# HC32F005.net
KiCad netlist of a schematic drawn in Altium Designer
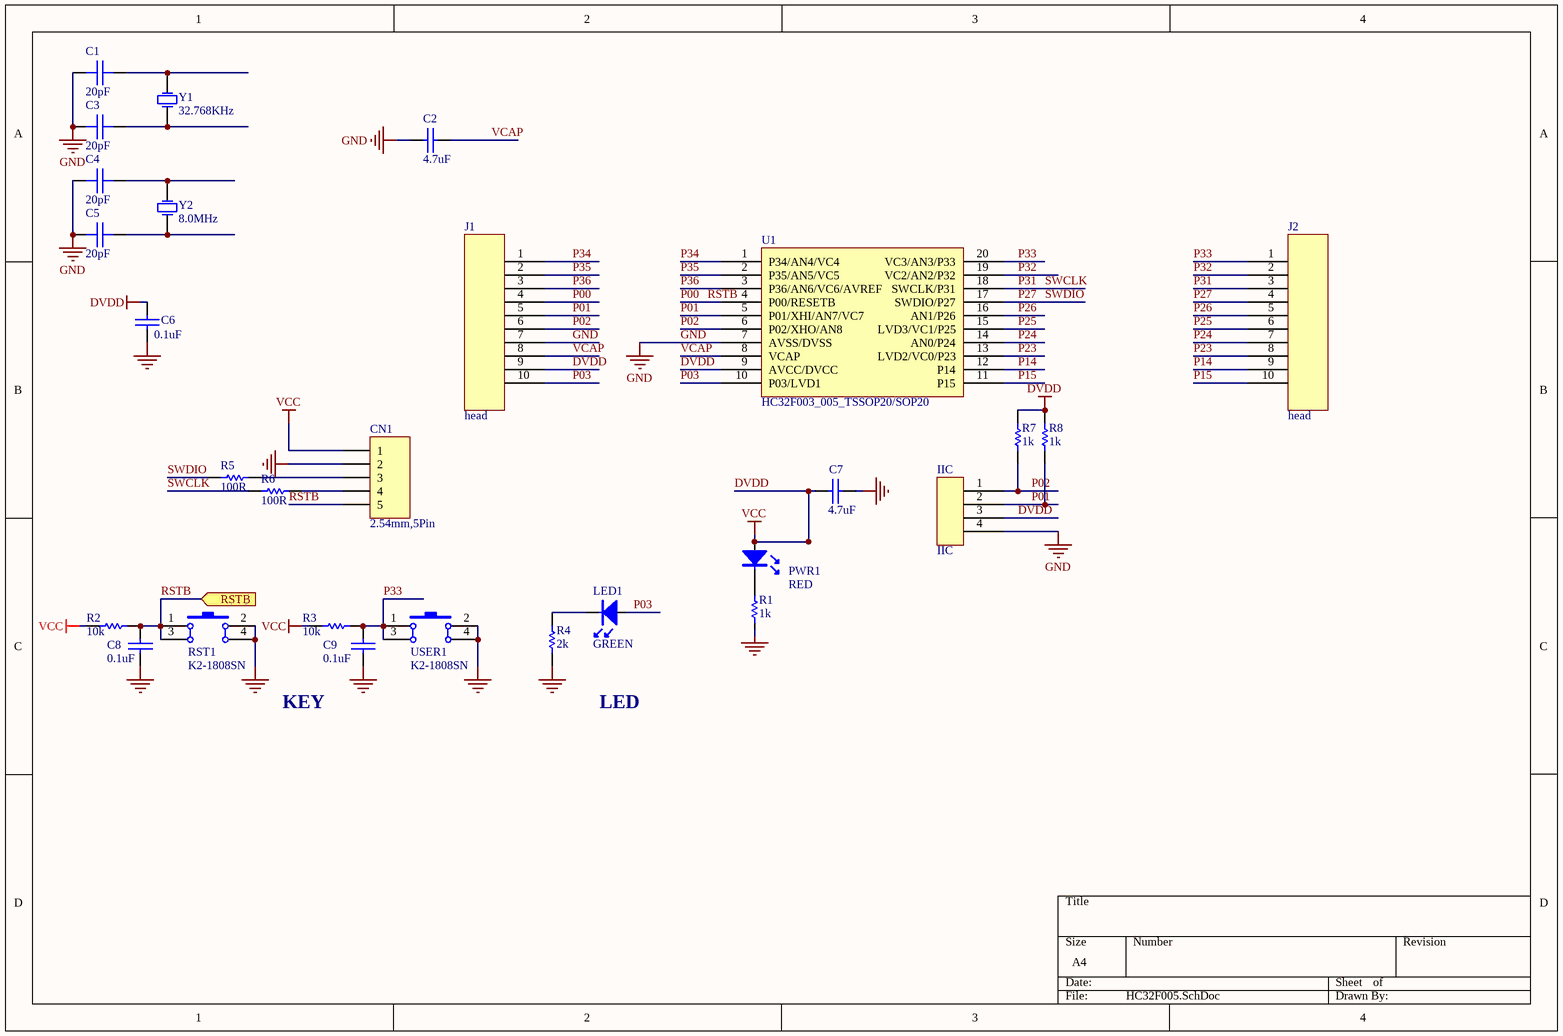
[diagram p0: HC32F005.SchDoc]

(export (version "E")
  (design (tool "Eeschema 10.0.6"))
  (components
    (comp (ref "C1")
      (value "20pF")
      (footprint "C0603")
      (description "Capacitor without polarity")
      (libsource (lib "STK-HC32L110_F003_005-TSSOP20-V2.0") (part "C_no pol"))
    )
    (comp (ref "C2")
      (value "4.7uF")
      (footprint "C0603")
      (description "Capacitor")
      (libsource (lib "STK-HC32L110_F003_005-TSSOP20-V2.0") (part "CAP-CC(SMD)"))
    )
    (comp (ref "C3")
      (value "20pF")
      (footprint "C0603")
      (description "Capacitor without polarity")
      (libsource (lib "STK-HC32L110_F003_005-TSSOP20-V2.0") (part "C_no pol"))
    )
    (comp (ref "C4")
      (value "20pF")
      (footprint "C0603")
      (description "Capacitor without polarity")
      (libsource (lib "STK-HC32L110_F003_005-TSSOP20-V2.0") (part "C_no pol"))
    )
    (comp (ref "C5")
      (value "20pF")
      (footprint "C0603")
      (description "Capacitor without polarity")
      (libsource (lib "STK-HC32L110_F003_005-TSSOP20-V2.0") (part "C_no pol"))
    )
    (comp (ref "C6")
      (value "0.1uF")
      (footprint "C0603")
      (description "Ceramic Capacitor,0603")
      (libsource (lib "MyLib_Altium") (part "CAP-CC(SMD)"))
    )
    (comp (ref "C7")
      (value "4.7uF")
      (footprint "C0603")
      (description "Ceramic Capacitor,0603")
      (libsource (lib "MyLib_Altium") (part "CAP-CC(SMD)"))
    )
    (comp (ref "C8")
      (value "0.1uF")
      (footprint "C0603")
      (description "Ceramic Capacitor,0603")
      (libsource (lib "MyLib_Altium") (part "CAP-CC(SMD)"))
    )
    (comp (ref "C9")
      (value "0.1uF")
      (footprint "C0603")
      (description "Ceramic Capacitor,0603")
      (libsource (lib "MyLib_Altium") (part "CAP-CC(SMD)"))
    )
    (comp (ref "CN1")
      (value "2.54mm,5Pin")
      (footprint "HDR1X5")
      (description "Header, 5-Pin")
      (fields (field (name "PUBLISHER") "Altium Limited"))
      (libsource (lib "STK-HC32L110_F003_005-TSSOP20-V2.0") (part "Header 5"))
    )
    (comp (ref "IIC")
      (value "IIC")
      (footprint "HDR1X4")
      (libsource (lib "altium-import") (part "root_0_IIC_"))
    )
    (comp (ref "J1")
      (value "head")
      (footprint "HDR1*10")
      (libsource (lib "altium-import") (part "root_0_mirrored_Component_1_"))
    )
    (comp (ref "J2")
      (value "head")
      (footprint "HC32F005:HDR1*10")
      (libsource (lib "altium-import") (part "root_0_Component_1_"))
    )
    (comp (ref "LED1") (value "GREEN") (footprint "LED0603") (libsource (lib "MyLib_Altium") (part "LED")))
    (comp (ref "PWR1") (value "RED") (footprint "LED0603") (libsource (lib "MyLib_Altium") (part "LED")))
    (comp (ref "R1")
      (value "1k")
      (footprint "R0603")
      (description "Resister,0603,5%")
      (libsource (lib "MyLib_Altium") (part "RES"))
    )
    (comp (ref "R2")
      (value "10k")
      (footprint "R0603")
      (description "Resister,0603,5%")
      (libsource (lib "MyLib_Altium") (part "RES"))
    )
    (comp (ref "R3")
      (value "10k")
      (footprint "R0603")
      (description "Resister,0603,5%")
      (libsource (lib "MyLib_Altium") (part "RES"))
    )
    (comp (ref "R4")
      (value "2k")
      (footprint "R0603")
      (description "Resister,0603,5%")
      (libsource (lib "MyLib_Altium") (part "RES"))
    )
    (comp (ref "R5")
      (value "100R")
      (footprint "R0603")
      (description "Resister,0603,5%")
      (libsource (lib "MyLib_Altium") (part "RES"))
    )
    (comp (ref "R6")
      (value "100R")
      (footprint "R0603")
      (description "Resister,0603,5%")
      (libsource (lib "MyLib_Altium") (part "RES"))
    )
    (comp (ref "R7")
      (value "1k")
      (footprint "R0603")
      (description "Resister,0603,5%")
      (libsource (lib "MyLib_Altium") (part "RES"))
    )
    (comp (ref "R8")
      (value "1k")
      (footprint "R0603")
      (description "Resister,0603,5%")
      (libsource (lib "MyLib_Altium") (part "RES"))
    )
    (comp (ref "RST1")
      (value "K2-1808SN")
      (footprint "STK-HC32L110_F003_005-TSSOP20-V2.01:PUSHBUTTON-4.2*3.25")
      (description "SMD button")
      (libsource (lib "MyLib_Altium") (part "Button-SMD-6*6"))
    )
    (comp (ref "U1")
      (value "HC32F003_005_TSSOP20/SOP20")
      (footprint "STK-HC32L110_F003_005-TSSOP20-V2.01:TSSOP-20")
      (libsource (lib "HC32L110_F003_005") (part "HC32F003_005_TSSOP20/SOP20"))
    )
    (comp (ref "USER1")
      (value "K2-1808SN")
      (footprint "PUSHBUTTON-4.2*3.25")
      (description "SMD button")
      (libsource (lib "MyLib_Altium") (part "Button-SMD-6*6"))
    )
    (comp (ref "Y1")
      (value "32.768KHz")
      (footprint "32.768K")
      (description "4.0000MHz")
      (libsource (lib "STK-HC32L110_F003_005-TSSOP20-V2.0") (part "Crystal_1"))
    )
    (comp (ref "Y2")
      (value "8.0MHz")
      (footprint "49s")
      (description "4.0000MHz")
      (libsource (lib "STK-HC32L110_F003_005-TSSOP20-V2.0") (part "Crystal"))
    )
  )
  (nets
    (net (code "1") (name "/P00") (class "Default")
      (node (ref "C8") (pin "1") (pinfunction "1_1") (pintype "passive"))
      (node (ref "CN1") (pin "5") (pinfunction "5_5") (pintype "passive"))
      (node (ref "J1") (pin "4") (pinfunction "13_4") (pintype "passive"))
      (node (ref "R2") (pin "2") (pinfunction "2_2") (pintype "passive"))
      (node (ref "RST1") (pin "1") (pinfunction "1_1") (pintype "passive"))
      (node (ref "RST1") (pin "3") (pinfunction "3_3") (pintype "passive"))
      (node (ref "U1") (pin "4") (pinfunction "P00/RESETB_4") (pintype "passive"))
    )
    (net (code "2") (name "/P01") (class "Default")
      (node (ref "IIC") (pin "2") (pinfunction "2_2") (pintype "passive"))
      (node (ref "J1") (pin "5") (pinfunction "14_5") (pintype "passive"))
      (node (ref "R8") (pin "2") (pinfunction "2_2") (pintype "passive"))
      (node (ref "U1") (pin "5") (pinfunction "P01/XHI/AN7/VC7_5") (pintype "passive"))
    )
    (net (code "3") (name "/P02") (class "Default")
      (node (ref "IIC") (pin "1") (pinfunction "1_1") (pintype "passive"))
      (node (ref "J1") (pin "6") (pinfunction "15_6") (pintype "passive"))
      (node (ref "R7") (pin "2") (pinfunction "2_2") (pintype "passive"))
      (node (ref "U1") (pin "6") (pinfunction "P02/XHO/AN8_6") (pintype "passive"))
    )
    (net (code "4") (name "/P03") (class "Default")
      (node (ref "J1") (pin "10") (pinfunction "19_10") (pintype "passive"))
      (node (ref "LED1") (pin "1") (pinfunction "A_1") (pintype "passive"))
      (node (ref "U1") (pin "10") (pinfunction "P03/LVD1_10") (pintype "passive"))
    )
    (net (code "5") (name "/P14") (class "Default")
      (node (ref "J2") (pin "9") (pinfunction "18_9") (pintype "passive"))
      (node (ref "U1") (pin "12") (pinfunction "P14_12") (pintype "passive"))
    )
    (net (code "6") (name "/P15") (class "Default")
      (node (ref "J2") (pin "10") (pinfunction "19_10") (pintype "passive"))
      (node (ref "U1") (pin "11") (pinfunction "P15_11") (pintype "passive"))
    )
    (net (code "7") (name "/P23") (class "Default")
      (node (ref "J2") (pin "8") (pinfunction "17_8") (pintype "passive"))
      (node (ref "U1") (pin "13") (pinfunction "LVD2/VC0/P23_13") (pintype "passive"))
    )
    (net (code "8") (name "/P24") (class "Default")
      (node (ref "J2") (pin "7") (pinfunction "16_7") (pintype "passive"))
      (node (ref "U1") (pin "14") (pinfunction "AN0/P24_14") (pintype "passive"))
    )
    (net (code "9") (name "/P25") (class "Default")
      (node (ref "J2") (pin "6") (pinfunction "15_6") (pintype "passive"))
      (node (ref "U1") (pin "15") (pinfunction "LVD3/VC1/P25_15") (pintype "passive"))
    )
    (net (code "10") (name "/P26") (class "Default")
      (node (ref "J2") (pin "5") (pinfunction "14_5") (pintype "passive"))
      (node (ref "U1") (pin "16") (pinfunction "AN1/P26_16") (pintype "passive"))
    )
    (net (code "11") (name "/P27") (class "Default")
      (node (ref "J2") (pin "4") (pinfunction "13_4") (pintype "passive"))
      (node (ref "R5") (pin "2") (pinfunction "2_2") (pintype "passive"))
      (node (ref "U1") (pin "17") (pinfunction "SWDIO/P27_17") (pintype "passive"))
    )
    (net (code "12") (name "/P31") (class "Default")
      (node (ref "J2") (pin "3") (pinfunction "12_3") (pintype "passive"))
      (node (ref "R6") (pin "2") (pinfunction "2_2") (pintype "passive"))
      (node (ref "U1") (pin "18") (pinfunction "SWCLK/P31_18") (pintype "passive"))
    )
    (net (code "13") (name "/P32") (class "Default")
      (node (ref "J2") (pin "2") (pinfunction "11_2") (pintype "passive"))
      (node (ref "U1") (pin "19") (pinfunction "VC2/AN2/P32_19") (pintype "passive"))
    )
    (net (code "14") (name "/P33") (class "Default")
      (node (ref "C9") (pin "1") (pinfunction "1_1") (pintype "passive"))
      (node (ref "J2") (pin "1") (pinfunction "10_1") (pintype "passive"))
      (node (ref "R3") (pin "2") (pinfunction "2_2") (pintype "passive"))
      (node (ref "U1") (pin "20") (pinfunction "VC3/AN3/P33_20") (pintype "passive"))
      (node (ref "USER1") (pin "1") (pinfunction "1_1") (pintype "passive"))
      (node (ref "USER1") (pin "3") (pinfunction "3_3") (pintype "passive"))
    )
    (net (code "15") (name "/P34") (class "Default")
      (node (ref "J1") (pin "1") (pinfunction "10_1") (pintype "passive"))
      (node (ref "U1") (pin "1") (pinfunction "P34/AN4/VC4_1") (pintype "passive"))
    )
    (net (code "16") (name "/P35") (class "Default")
      (node (ref "J1") (pin "2") (pinfunction "11_2") (pintype "passive"))
      (node (ref "U1") (pin "2") (pinfunction "P35/AN5/VC5_2") (pintype "passive"))
    )
    (net (code "17") (name "/P36") (class "Default")
      (node (ref "J1") (pin "3") (pinfunction "12_3") (pintype "passive"))
      (node (ref "U1") (pin "3") (pinfunction "P36/AN6/VC6/AVREF_3") (pintype "passive"))
    )
    (net (code "18") (name "/VCAP") (class "Default")
      (node (ref "C2") (pin "2") (pinfunction "2_2") (pintype "passive"))
      (node (ref "J1") (pin "8") (pinfunction "17_8") (pintype "passive"))
      (node (ref "U1") (pin "8") (pinfunction "VCAP_8") (pintype "passive"))
    )
    (net (code "19") (name "DVDD") (class "Default")
      (node (ref "C6") (pin "1") (pinfunction "1_1") (pintype "passive"))
      (node (ref "C7") (pin "1") (pinfunction "1_1") (pintype "passive"))
      (node (ref "CN1") (pin "1") (pinfunction "1_1") (pintype "passive"))
      (node (ref "IIC") (pin "3") (pinfunction "3_3") (pintype "passive"))
      (node (ref "J1") (pin "9") (pinfunction "18_9") (pintype "passive"))
      (node (ref "PWR1") (pin "1") (pinfunction "A_1") (pintype "passive"))
      (node (ref "R2") (pin "1") (pinfunction "1_1") (pintype "passive"))
      (node (ref "R3") (pin "1") (pinfunction "1_1") (pintype "passive"))
      (node (ref "R7") (pin "1") (pinfunction "1_1") (pintype "passive"))
      (node (ref "R8") (pin "1") (pinfunction "1_1") (pintype "passive"))
      (node (ref "U1") (pin "9") (pinfunction "AVCC/DVCC_9") (pintype "passive"))
    )
    (net (code "20") (name "GND") (class "Default")
      (node (ref "C1") (pin "1") (pintype "passive"))
      (node (ref "C2") (pin "1") (pinfunction "1_1") (pintype "passive"))
      (node (ref "C3") (pin "1") (pintype "passive"))
      (node (ref "C4") (pin "2") (pintype "passive"))
      (node (ref "C5") (pin "2") (pintype "passive"))
      (node (ref "C6") (pin "2") (pinfunction "2_2") (pintype "passive"))
      (node (ref "C7") (pin "2") (pinfunction "2_2") (pintype "passive"))
      (node (ref "C8") (pin "2") (pinfunction "2_2") (pintype "passive"))
      (node (ref "C9") (pin "2") (pinfunction "2_2") (pintype "passive"))
      (node (ref "CN1") (pin "2") (pinfunction "2_2") (pintype "passive"))
      (node (ref "IIC") (pin "4") (pinfunction "4_4") (pintype "passive"))
      (node (ref "J1") (pin "7") (pinfunction "16_7") (pintype "passive"))
      (node (ref "R1") (pin "1") (pinfunction "1_1") (pintype "passive"))
      (node (ref "R4") (pin "1") (pinfunction "1_1") (pintype "passive"))
      (node (ref "RST1") (pin "2") (pinfunction "2_2") (pintype "passive"))
      (node (ref "RST1") (pin "4") (pinfunction "4_4") (pintype "passive"))
      (node (ref "U1") (pin "7") (pinfunction "AVSS/DVSS_7") (pintype "passive"))
      (node (ref "USER1") (pin "2") (pinfunction "2_2") (pintype "passive"))
      (node (ref "USER1") (pin "4") (pinfunction "4_4") (pintype "passive"))
    )
    (net (code "21") (name "Net-(C1-Pad2)") (class "Default")
      (node (ref "C1") (pin "2") (pintype "passive"))
      (node (ref "Y1") (pin "2") (pinfunction "2_2") (pintype "passive"))
    )
    (net (code "22") (name "Net-(C3-Pad2)") (class "Default")
      (node (ref "C3") (pin "2") (pintype "passive"))
      (node (ref "Y1") (pin "1") (pinfunction "1_1") (pintype "passive"))
    )
    (net (code "23") (name "Net-(C4-Pad1)") (class "Default")
      (node (ref "C4") (pin "1") (pintype "passive"))
      (node (ref "Y2") (pin "2") (pinfunction "2_2") (pintype "passive"))
    )
    (net (code "24") (name "Net-(C5-Pad1)") (class "Default")
      (node (ref "C5") (pin "1") (pintype "passive"))
      (node (ref "Y2") (pin "1") (pinfunction "1_1") (pintype "passive"))
    )
    (net (code "25") (name "Net-(CN1-Pad3)") (class "Default")
      (node (ref "CN1") (pin "3") (pinfunction "3_3") (pintype "passive"))
      (node (ref "R5") (pin "1") (pinfunction "1_1") (pintype "passive"))
    )
    (net (code "26") (name "Net-(CN1-Pad4)") (class "Default")
      (node (ref "CN1") (pin "4") (pinfunction "4_4") (pintype "passive"))
      (node (ref "R6") (pin "1") (pinfunction "1_1") (pintype "passive"))
    )
    (net (code "27") (name "Net-(LED1-K)") (class "Default")
      (node (ref "LED1") (pin "2") (pinfunction "K_2") (pintype "passive"))
      (node (ref "R4") (pin "2") (pinfunction "2_2") (pintype "passive"))
    )
    (net (code "28") (name "Net-(PWR1-K)") (class "Default")
      (node (ref "PWR1") (pin "2") (pinfunction "K_2") (pintype "passive"))
      (node (ref "R1") (pin "2") (pinfunction "2_2") (pintype "passive"))
    )
  )
)
